# v1.net
KiCad netlist of a schematic drawn in EAGLE
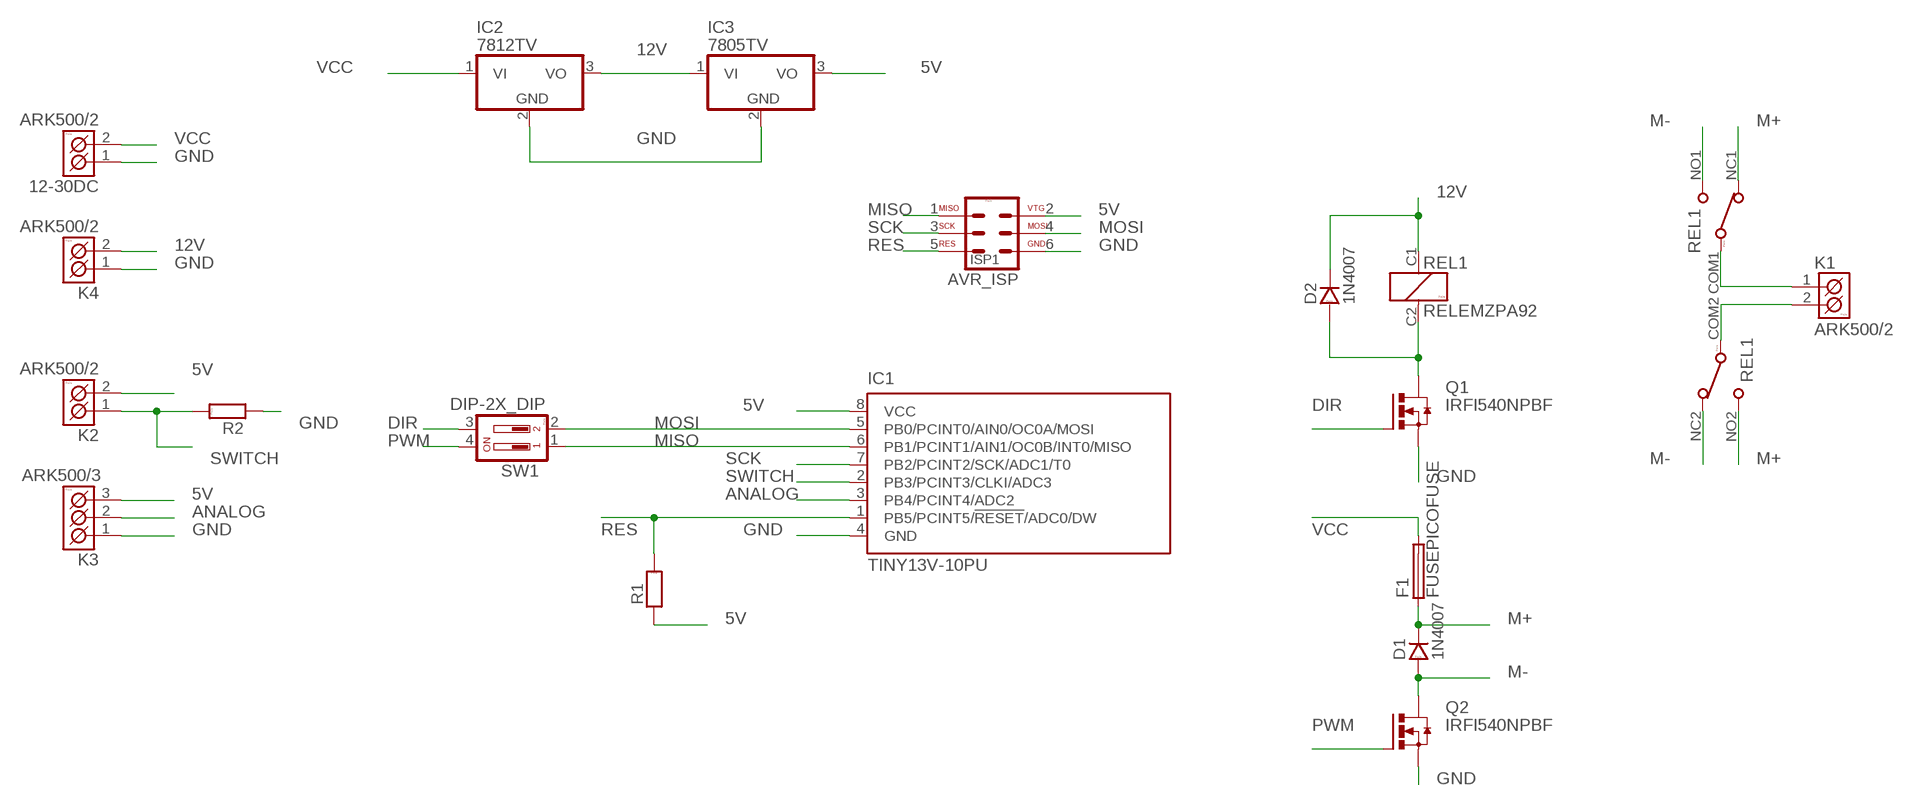
[diagram p0: schematic, sheet 1]

(export (version "E")
  (design (tool "Eeschema 10.0.6"))
  (components
    (comp (ref "12-30DC")
      (value "ARK500/2")
      (footprint "eagle-import:ARK500_2")
      (libsource (lib "eagle-import") (part "ARK500/2"))
    )
    (comp (ref "D1")
      (value "1N4007")
      (footprint "eagle-import:DO41")
      (libsource (lib "eagle-import") (part "1N4007"))
    )
    (comp (ref "D2")
      (value "1N4007")
      (footprint "eagle-import:DO41")
      (libsource (lib "eagle-import") (part "1N4007"))
    )
    (comp (ref "F1")
      (value "FUSEPICOFUSE")
      (footprint "eagle-import:PICOFUSE")
      (libsource (lib "eagle-import") (part "FUSEPICOFUSE"))
    )
    (comp (ref "IC1")
      (value "TINY13V-10PU")
      (footprint "eagle-import:DIL08")
      (fields (field (name "MPN") "ATTINY13V-10PU"))
      (libsource (lib "eagle-import") (part "TINY13PUV-10"))
    )
    (comp (ref "IC2")
      (value "7812TV")
      (footprint "eagle-import:TO220V")
      (libsource (lib "eagle-import") (part "78TV12"))
    )
    (comp (ref "IC3")
      (value "7805TV")
      (footprint "eagle-import:TO220V")
      (libsource (lib "eagle-import") (part "78TV05"))
    )
    (comp (ref "ISP1")
      (value "AVR_ISP")
      (footprint "eagle-import:MLW06G")
      (libsource (lib "eagle-import") (part "AVR_ISP"))
    )
    (comp (ref "K1")
      (value "ARK500/2")
      (footprint "eagle-import:ARK500_2")
      (libsource (lib "eagle-import") (part "ARK500/2"))
    )
    (comp (ref "K2")
      (value "ARK500/2")
      (footprint "eagle-import:ARK500_2")
      (libsource (lib "eagle-import") (part "ARK500/2"))
    )
    (comp (ref "K3")
      (value "ARK500/3")
      (footprint "eagle-import:ARK500_3")
      (libsource (lib "eagle-import") (part "ARK500/3"))
    )
    (comp (ref "K4")
      (value "ARK500/2")
      (footprint "eagle-import:ARK500_2")
      (libsource (lib "eagle-import") (part "ARK500/2"))
    )
    (comp (ref "Q1")
      (value "IRFI540NPBF")
      (footprint "eagle-import:TO220BH")
      (libsource (lib "eagle-import") (part "IRFI540NPBF"))
    )
    (comp (ref "Q2")
      (value "IRFI540NPBF")
      (footprint "eagle-import:TO220BH")
      (libsource (lib "eagle-import") (part "IRFI540NPBF"))
    )
    (comp (ref "R1")
      (value "R_7,5")
      (footprint "eagle-import:R-7,5")
      (libsource (lib "eagle-import") (part "R_7,5"))
    )
    (comp (ref "R2")
      (value "R_7,5")
      (footprint "eagle-import:R-7,5")
      (libsource (lib "eagle-import") (part "R_7,5"))
    )
    (comp (ref "REL1")
      (value "RELEMZPA92")
      (footprint "eagle-import:RELEMZPA92")
      (libsource (lib "eagle-import") (part "RELEMZPA92"))
    )
    (comp (ref "SW1")
      (value "DIP-2X_DIP")
      (footprint "eagle-import:DIP-2X")
      (libsource (lib "eagle-import") (part "DIP-2X_DIP"))
    )
  )
  (nets
    (net (code "1") (name "/5V") (class "Default")
      (node (ref "IC1") (pin "8") (pinfunction "VCC_8") (pintype "power_in"))
      (node (ref "IC3") (pin "3") (pinfunction "VO_3") (pintype "passive"))
      (node (ref "ISP1") (pin "2") (pinfunction "2_2") (pintype "passive"))
      (node (ref "K2") (pin "2") (pinfunction "K2_2") (pintype "passive"))
      (node (ref "K3") (pin "3") (pinfunction "K3_3") (pintype "passive"))
      (node (ref "R1") (pin "1") (pinfunction "1_1") (pintype "passive"))
    )
    (net (code "2") (name "/12V") (class "Default")
      (node (ref "D2") (pin "K") (pinfunction "K_K") (pintype "passive"))
      (node (ref "IC2") (pin "3") (pinfunction "VO_3") (pintype "passive"))
      (node (ref "IC3") (pin "1") (pinfunction "VI_1") (pintype "input"))
      (node (ref "K4") (pin "2") (pinfunction "K2_2") (pintype "passive"))
      (node (ref "REL1") (pin "C1") (pinfunction "C1_C1") (pintype "passive"))
    )
    (net (code "3") (name "/ANALOG") (class "Default")
      (node (ref "IC1") (pin "3") (pinfunction "PB4/PCINT4/ADC2_3") (pintype "bidirectional"))
      (node (ref "K3") (pin "2") (pinfunction "K2_2") (pintype "passive"))
    )
    (net (code "4") (name "/DIR") (class "Default")
      (node (ref "Q1") (pin "G") (pinfunction "G_G") (pintype "passive"))
      (node (ref "SW1") (pin "3") (pinfunction "3_3") (pintype "passive"))
    )
    (net (code "5") (name "/GND") (class "Default")
      (node (ref "12-30DC") (pin "1") (pinfunction "K1_1") (pintype "passive"))
      (node (ref "IC1") (pin "4") (pinfunction "GND_4") (pintype "power_in"))
      (node (ref "IC2") (pin "2") (pinfunction "GND_2") (pintype "passive"))
      (node (ref "IC3") (pin "2") (pinfunction "GND_2") (pintype "passive"))
      (node (ref "ISP1") (pin "6") (pinfunction "6_6") (pintype "passive"))
      (node (ref "K3") (pin "1") (pinfunction "K1_1") (pintype "passive"))
      (node (ref "K4") (pin "1") (pinfunction "K1_1") (pintype "passive"))
      (node (ref "Q1") (pin "S") (pinfunction "S_S") (pintype "passive"))
      (node (ref "Q2") (pin "S") (pinfunction "S_S") (pintype "passive"))
      (node (ref "R2") (pin "1") (pinfunction "1_1") (pintype "passive"))
    )
    (net (code "6") (name "/M+") (class "Default")
      (node (ref "D1") (pin "K") (pinfunction "K_K") (pintype "passive"))
      (node (ref "F1") (pin "1") (pinfunction "1_1") (pintype "passive"))
      (node (ref "REL1") (pin "NC1") (pinfunction "NC_NC1") (pintype "passive"))
      (node (ref "REL1") (pin "NO2") (pinfunction "NO_NO2") (pintype "passive"))
    )
    (net (code "7") (name "/M-") (class "Default")
      (node (ref "D1") (pin "A") (pinfunction "A_A") (pintype "passive"))
      (node (ref "Q2") (pin "D") (pinfunction "D_D") (pintype "passive"))
      (node (ref "REL1") (pin "NC2") (pinfunction "NC_NC2") (pintype "passive"))
      (node (ref "REL1") (pin "NO1") (pinfunction "NO_NO1") (pintype "passive"))
    )
    (net (code "8") (name "/MISO") (class "Default")
      (node (ref "IC1") (pin "6") (pinfunction "PB1/PCINT1/AIN1/OC0B/INT0/MISO_6") (pintype "bidirectional"))
      (node (ref "ISP1") (pin "1") (pinfunction "1_1") (pintype "passive"))
      (node (ref "SW1") (pin "1") (pinfunction "1_1") (pintype "passive"))
    )
    (net (code "9") (name "/MOSI") (class "Default")
      (node (ref "IC1") (pin "5") (pinfunction "PB0/PCINT0/AIN0/OC0A/MOSI_5") (pintype "bidirectional"))
      (node (ref "ISP1") (pin "4") (pinfunction "4_4") (pintype "passive"))
      (node (ref "SW1") (pin "2") (pinfunction "2_2") (pintype "passive"))
    )
    (net (code "10") (name "/PWM") (class "Default")
      (node (ref "Q2") (pin "G") (pinfunction "G_G") (pintype "passive"))
      (node (ref "SW1") (pin "4") (pinfunction "4_4") (pintype "passive"))
    )
    (net (code "11") (name "/RES") (class "Default")
      (node (ref "IC1") (pin "1") (pinfunction "PB5/PCINT5/~{RESET}/ADC0/DW_1") (pintype "bidirectional"))
      (node (ref "ISP1") (pin "5") (pinfunction "5_5") (pintype "passive"))
      (node (ref "R1") (pin "2") (pinfunction "2_2") (pintype "passive"))
    )
    (net (code "12") (name "/SCK") (class "Default")
      (node (ref "IC1") (pin "7") (pinfunction "PB2/PCINT2/SCK/ADC1/T0_7") (pintype "bidirectional"))
      (node (ref "ISP1") (pin "3") (pinfunction "3_3") (pintype "passive"))
    )
    (net (code "13") (name "/SWITCH") (class "Default")
      (node (ref "IC1") (pin "2") (pinfunction "PB3/PCINT3/CLKI/ADC3_2") (pintype "bidirectional"))
      (node (ref "K2") (pin "1") (pinfunction "K1_1") (pintype "passive"))
      (node (ref "R2") (pin "2") (pinfunction "2_2") (pintype "passive"))
    )
    (net (code "14") (name "/VCC") (class "Default")
      (node (ref "12-30DC") (pin "2") (pinfunction "K2_2") (pintype "passive"))
      (node (ref "F1") (pin "2") (pinfunction "2_2") (pintype "passive"))
      (node (ref "IC2") (pin "1") (pinfunction "VI_1") (pintype "input"))
    )
    (net (code "15") (name "Net-(D2-PadA)") (class "Default")
      (node (ref "D2") (pin "A") (pinfunction "A_A") (pintype "passive"))
      (node (ref "Q1") (pin "D") (pinfunction "D_D") (pintype "passive"))
      (node (ref "REL1") (pin "C2") (pinfunction "C2_C2") (pintype "passive"))
    )
    (net (code "16") (name "Net-(K1-K1)") (class "Default")
      (node (ref "K1") (pin "1") (pinfunction "K1_1") (pintype "passive"))
      (node (ref "REL1") (pin "COM1") (pinfunction "COM_COM1") (pintype "passive"))
    )
    (net (code "17") (name "Net-(K1-K2)") (class "Default")
      (node (ref "K1") (pin "2") (pinfunction "K2_2") (pintype "passive"))
      (node (ref "REL1") (pin "COM2") (pinfunction "COM_COM2") (pintype "passive"))
    )
  )
)
